# Connectors.net
KiCad netlist of a schematic drawn in Altium Designer
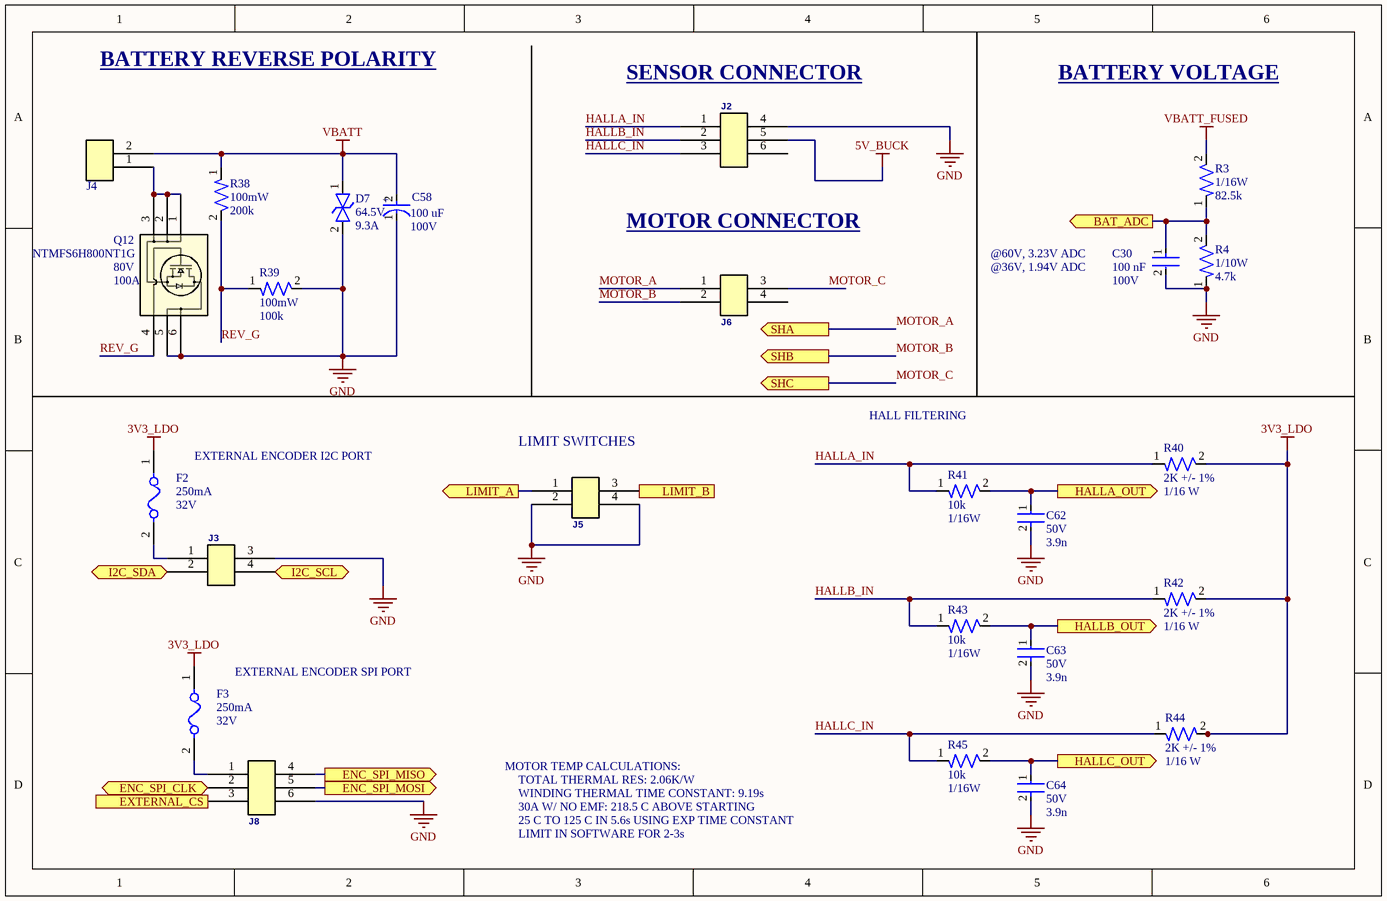
[diagram p0: Connectors.SchDoc]

(export (version "E")
  (design (tool "Eeschema 10.0.6"))
  (components
    (comp (ref "C30")
      (value "GRM188R72A104KA35D")
      (footprint "CAP-0603")
      (description "CAP CER 100NF 100V X7R 0603")
      (fields (field (name "CAPACITANCE") "100 nF") (field (name "VOLTAGE") "100V"))
      (libsource (lib "JLC_25") (part "CAP-1U-0002"))
    )
    (comp (ref "C58")
      (value "EEETK2A101AM")
      (footprint "CAP-100U-0001")
      (description "CAP ALUM 100UF 20% 100V SMD")
      (fields (field (name "VOLTAGE") "100V") (field (name "CAPACITANCE") "100 uF"))
      (libsource (lib "JLC_25") (part "CAP-100U-0001"))
    )
    (comp (ref "C62")
      (value "CC0402JRX7R9BB392")
      (footprint "CAP-0402")
      (description "3900 pF ±5% 50V Ceramic Capacitor X7R 0402 (1005 Metric)")
      (fields (field (name "VOLTAGE") "50V") (field (name "CAPACITANCE") "3.9n"))
      (libsource (lib "JLC_25") (part "CAP-3.9N-0001"))
    )
    (comp (ref "C63")
      (value "CC0402JRX7R9BB392")
      (footprint "CAP-0402")
      (description "3900 pF ±5% 50V Ceramic Capacitor X7R 0402 (1005 Metric)")
      (fields (field (name "VOLTAGE") "50V") (field (name "CAPACITANCE") "3.9n"))
      (libsource (lib "JLC_25") (part "CAP-3.9N-0001"))
    )
    (comp (ref "C64")
      (value "CC0402JRX7R9BB392")
      (footprint "CAP-0402")
      (description "3900 pF ±5% 50V Ceramic Capacitor X7R 0402 (1005 Metric)")
      (fields (field (name "VOLTAGE") "50V") (field (name "CAPACITANCE") "3.9n"))
      (libsource (lib "JLC_25") (part "CAP-3.9N-0001"))
    )
    (comp (ref "D7")
      (value "SMBJ40CA")
      (footprint "DO-214AA (SMBJ)")
      (description "TVS DIODE 40VWM 64.5VC DO214AA")
      (fields (field (name "VOLTAGE RATING") "64.5V") (field (name "CURRENT RATING") "9.3A"))
      (libsource (lib "JLC_25") (part "DIO-TVS-0001"))
    )
    (comp (ref "F2")
      (value "0467.250NRHF")
      (footprint "RES-0603")
      (description "FUSE BRD MT 250MA 32VAC 32VDC")
      (fields (field (name "FUSE CURRENT") "250mA") (field (name "VOLTAGE RATING") "32V"))
      (libsource (lib "JLC_25") (part "FUSE-0002"))
    )
    (comp (ref "F3")
      (value "0467.250NRHF")
      (footprint "RES-0603")
      (description "FUSE BRD MT 250MA 32VAC 32VDC")
      (fields (field (name "FUSE CURRENT") "250mA") (field (name "VOLTAGE RATING") "32V"))
      (libsource (lib "JLC_25") (part "FUSE-0002"))
    )
    (comp (ref "J2")
      (value "Molex 43045-0612")
      (footprint "CONN-6POS-0001")
      (description "CONN HEADER VERT 6POS 3MM")
      (libsource (lib "JLC_25") (part "CONN-6POS-0001"))
    )
    (comp (ref "J3")
      (value "Molex 43045-0412")
      (footprint "CONN-4POS-0002")
      (description "CONN HEADER VERT 4POS 3MM")
      (libsource (lib "JLC_25") (part "CONN-4POS-0002"))
    )
    (comp (ref "J4")
      (value "1546927-2")
      (footprint "CONN-1546927-2")
      (libsource (lib "JLC_25") (part "CONN-2POS-0003"))
    )
    (comp (ref "J5")
      (value "Molex 43045-0412")
      (footprint "CONN-4POS-0002")
      (description "CONN HEADER VERT 4POS 3MM")
      (libsource (lib "JLC_25") (part "CONN-4POS-0002"))
    )
    (comp (ref "J6")
      (value "Molex 43045-0412")
      (footprint "CONN-4POS-0002")
      (description "CONN HEADER VERT 4POS 3MM")
      (libsource (lib "JLC_25") (part "CONN-4POS-0002"))
    )
    (comp (ref "J8")
      (value "Molex 43045-0612")
      (footprint "CONN-6POS-0001")
      (description "CONN HEADER VERT 6POS 3MM")
      (libsource (lib "JLC_25") (part "CONN-6POS-0001"))
    )
    (comp (ref "Q12")
      (value "NTMFS6H800NT1G")
      (footprint "DFN6_5X6_SO8FL_488AA_ONS")
      (description "N-Channel 80 V 28A (Ta), 203A (Tc) 3.8W (Ta), 200W (Tc) Surface Mount 5-DFN (5x6) (8-SOFL)")
      (fields
        (field (name "MANUFACTURER_PART_NUMBER") "TPH2R506PL")
        (field (name "VDSS") "80V")
        (field (name "DRAIN CURRENT") "100A")
      )
      (libsource (lib "MasterLib") (part "NTMFS6H800NT1G"))
    )
    (comp (ref "R3")
      (value "RC0402FR-0782K5L")
      (footprint "RES-0402")
      (description "82.5 kOhms ±1% 0.063W, 1/16W Chip Resistor 0402 (1005 Metric) Moisture Resistant Thick Film")
      (fields
        (field (name "TOLERANCE") "1%")
        (field (name "POWER") "1/16W")
        (field (name "RESISTANCE") "82.5k")
      )
      (libsource (lib "JLC_25") (part "RES-82.5k-0001"))
    )
    (comp (ref "R4")
      (value "RC0603FR-074K7L")
      (footprint "RES-0603")
      (description "RES 4.7K OHM 1% 1/10W 0603")
      (fields
        (field (name "TOLERANCE") "1%")
        (field (name "POWER") "1/10W")
        (field (name "RESISTANCE") "4.7k")
      )
      (libsource (lib "JLC_25") (part "RES-4.7k-0001"))
    )
    (comp (ref "R38")
      (value "RC0603FR-07200KL")
      (footprint "RES-0603")
      (description "RES SMD 200K OHM 1% 1/10W 0603")
      (fields
        (field (name "TOLERANCE") "1%")
        (field (name "POWER") "100mW")
        (field (name "RESISTANCE") "200k")
      )
      (libsource (lib "JLC_25") (part "RES-200k-0001"))
    )
    (comp (ref "R39")
      (value "RC0603FR-07100KL")
      (footprint "RES-0603")
      (description "RES SMD 100K OHM 1% 1/10W 0603")
      (fields
        (field (name "TOLERANCE") "1%")
        (field (name "POWER") "100mW")
        (field (name "RESISTANCE") "100k")
      )
      (libsource (lib "JLC_25") (part "RES-100k-0001"))
    )
    (comp (ref "R40")
      (value "RC0402FR-072KP")
      (footprint "RES-0402")
      (description "2 kOhms ±1% 0.063W, 1/16W Chip Resistor 0402 (1005 Metric) Thick Film")
      (fields (field (name "RESISTANCE") "2K +/- 1%") (field (name "POWER") "1/16 W"))
      (libsource (lib "MasterLib") (part "RES-2K-0001"))
    )
    (comp (ref "R41")
      (value "RC0402FR-0710KL")
      (footprint "RES-0402")
      (description "RES 10K OHM 1% 1/16W 0402")
      (fields
        (field (name "TOLERANCE") "1%")
        (field (name "RESISTANCE") "10k")
        (field (name "POWER") "1/16W")
      )
      (libsource (lib "JLC_25") (part "RES-10k-0001"))
    )
    (comp (ref "R42")
      (value "RC0402FR-072KP")
      (footprint "RES-0402")
      (description "2 kOhms ±1% 0.063W, 1/16W Chip Resistor 0402 (1005 Metric) Thick Film")
      (fields (field (name "RESISTANCE") "2K +/- 1%") (field (name "POWER") "1/16 W"))
      (libsource (lib "MasterLib") (part "RES-2K-0001"))
    )
    (comp (ref "R43")
      (value "RC0402FR-0710KL")
      (footprint "RES-0402")
      (description "RES 10K OHM 1% 1/16W 0402")
      (fields
        (field (name "TOLERANCE") "1%")
        (field (name "RESISTANCE") "10k")
        (field (name "POWER") "1/16W")
      )
      (libsource (lib "JLC_25") (part "RES-10k-0001"))
    )
    (comp (ref "R44")
      (value "RC0402FR-072KP")
      (footprint "RES-0402")
      (description "2 kOhms ±1% 0.063W, 1/16W Chip Resistor 0402 (1005 Metric) Thick Film")
      (fields (field (name "RESISTANCE") "2K +/- 1%") (field (name "POWER") "1/16 W"))
      (libsource (lib "MasterLib") (part "RES-2K-0001"))
    )
    (comp (ref "R45")
      (value "RC0402FR-0710KL")
      (footprint "RES-0402")
      (description "RES 10K OHM 1% 1/16W 0402")
      (fields
        (field (name "TOLERANCE") "1%")
        (field (name "RESISTANCE") "10k")
        (field (name "POWER") "1/16W")
      )
      (libsource (lib "JLC_25") (part "RES-10k-0001"))
    )
  )
  (nets
    (net (code "1") (name "/BAT_ADC") (class "Default")
      (node (ref "C30") (pin "1") (pinfunction "1_1") (pintype "passive"))
      (node (ref "R3") (pin "1") (pinfunction "1_1") (pintype "passive"))
      (node (ref "R4") (pin "2") (pinfunction "2_2") (pintype "passive"))
    )
    (net (code "2") (name "/ENC_SPI_CLK") (class "Default")
      (node (ref "J8") (pin "2") (pinfunction "2_2") (pintype "passive"))
    )
    (net (code "3") (name "/ENC_SPI_MISO") (class "Default")
      (node (ref "J8") (pin "4") (pinfunction "4_4") (pintype "passive"))
    )
    (net (code "4") (name "/ENC_SPI_MOSI") (class "Default")
      (node (ref "J8") (pin "5") (pinfunction "5_5") (pintype "passive"))
    )
    (net (code "5") (name "/EXTERNAL_CS") (class "Default")
      (node (ref "J8") (pin "3") (pinfunction "3_3") (pintype "passive"))
    )
    (net (code "6") (name "/HALLA_IN") (class "Default")
      (node (ref "J2") (pin "1") (pinfunction "7_1") (pintype "passive"))
      (node (ref "R40") (pin "1") (pinfunction "1_1") (pintype "passive"))
      (node (ref "R41") (pin "1") (pinfunction "1_1") (pintype "passive"))
    )
    (net (code "7") (name "/HALLA_OUT") (class "Default")
      (node (ref "C62") (pin "1") (pinfunction "1_1") (pintype "passive"))
      (node (ref "R41") (pin "2") (pinfunction "2_2") (pintype "passive"))
    )
    (net (code "8") (name "/HALLB_IN") (class "Default")
      (node (ref "J2") (pin "2") (pinfunction "2_2") (pintype "passive"))
      (node (ref "R42") (pin "1") (pinfunction "1_1") (pintype "passive"))
      (node (ref "R43") (pin "1") (pinfunction "1_1") (pintype "passive"))
    )
    (net (code "9") (name "/HALLB_OUT") (class "Default")
      (node (ref "C63") (pin "1") (pinfunction "1_1") (pintype "passive"))
      (node (ref "R43") (pin "2") (pinfunction "2_2") (pintype "passive"))
    )
    (net (code "10") (name "/HALLC_IN") (class "Default")
      (node (ref "J2") (pin "3") (pinfunction "3_3") (pintype "passive"))
      (node (ref "R44") (pin "1") (pinfunction "1_1") (pintype "passive"))
      (node (ref "R45") (pin "1") (pinfunction "1_1") (pintype "passive"))
    )
    (net (code "11") (name "/HALLC_OUT") (class "Default")
      (node (ref "C64") (pin "1") (pinfunction "1_1") (pintype "passive"))
      (node (ref "R45") (pin "2") (pinfunction "2_2") (pintype "passive"))
    )
    (net (code "12") (name "/I2C_SCL") (class "Default")
      (node (ref "J3") (pin "4") (pinfunction "4_4") (pintype "passive"))
    )
    (net (code "13") (name "/I2C_SDA") (class "Default")
      (node (ref "J3") (pin "2") (pinfunction "2_2") (pintype "passive"))
    )
    (net (code "14") (name "/LIMIT_A") (class "Default")
      (node (ref "J5") (pin "1") (pinfunction "1_1") (pintype "passive"))
    )
    (net (code "15") (name "/LIMIT_B") (class "Default")
      (node (ref "J5") (pin "3") (pinfunction "3_3") (pintype "passive"))
    )
    (net (code "16") (name "/MOTOR_A") (class "Default")
      (node (ref "J6") (pin "1") (pinfunction "1_1") (pintype "passive"))
    )
    (net (code "17") (name "/MOTOR_B") (class "Default")
      (node (ref "J6") (pin "2") (pinfunction "2_2") (pintype "passive"))
    )
    (net (code "18") (name "/MOTOR_C") (class "Default")
      (node (ref "J6") (pin "3") (pinfunction "3_3") (pintype "passive"))
    )
    (net (code "19") (name "/REV_G") (class "Default")
      (node (ref "Q12") (pin "4") (pinfunction "4_4") (pintype "passive"))
      (node (ref "R38") (pin "2") (pinfunction "2_2") (pintype "passive"))
      (node (ref "R39") (pin "1") (pinfunction "1_1") (pintype "passive"))
    )
    (net (code "20") (name "3V3_LDO") (class "Default")
      (node (ref "F2") (pin "1") (pinfunction "1_1") (pintype "passive"))
      (node (ref "F3") (pin "1") (pinfunction "1_1") (pintype "passive"))
      (node (ref "R40") (pin "2") (pinfunction "2_2") (pintype "passive"))
      (node (ref "R42") (pin "2") (pinfunction "2_2") (pintype "passive"))
      (node (ref "R44") (pin "2") (pinfunction "2_2") (pintype "passive"))
    )
    (net (code "21") (name "5V_BUCK") (class "Default")
      (node (ref "J2") (pin "5") (pinfunction "5_5") (pintype "passive"))
    )
    (net (code "22") (name "GND") (class "Default")
      (node (ref "C30") (pin "2") (pinfunction "2_2") (pintype "passive"))
      (node (ref "C58") (pin "1") (pinfunction "2_1") (pintype "passive"))
      (node (ref "C62") (pin "2") (pinfunction "2_2") (pintype "passive"))
      (node (ref "C63") (pin "2") (pinfunction "2_2") (pintype "passive"))
      (node (ref "C64") (pin "2") (pinfunction "2_2") (pintype "passive"))
      (node (ref "D7") (pin "2") (pintype "passive"))
      (node (ref "J2") (pin "4") (pinfunction "4_4") (pintype "passive"))
      (node (ref "J3") (pin "3") (pinfunction "3_3") (pintype "passive"))
      (node (ref "J5") (pin "2") (pinfunction "2_2") (pintype "passive"))
      (node (ref "J5") (pin "4") (pinfunction "4_4") (pintype "passive"))
      (node (ref "J8") (pin "6") (pinfunction "6_6") (pintype "passive"))
      (node (ref "Q12") (pin "5") (pinfunction "5_5") (pintype "passive"))
      (node (ref "Q12") (pin "6") (pinfunction "6_6") (pintype "passive"))
      (node (ref "R39") (pin "2") (pinfunction "2_2") (pintype "passive"))
      (node (ref "R4") (pin "1") (pinfunction "1_1") (pintype "passive"))
    )
    (net (code "23") (name "Net-(F2-Pad2)") (class "Default")
      (node (ref "F2") (pin "2") (pinfunction "2_2") (pintype "passive"))
      (node (ref "J3") (pin "1") (pinfunction "1_1") (pintype "passive"))
    )
    (net (code "24") (name "Net-(J4-7)") (class "Default")
      (node (ref "J4") (pin "1") (pinfunction "7_1") (pintype "passive"))
      (node (ref "Q12") (pin "1") (pinfunction "1_1") (pintype "passive"))
      (node (ref "Q12") (pin "2") (pinfunction "2_2") (pintype "passive"))
      (node (ref "Q12") (pin "3") (pinfunction "3_3") (pintype "passive"))
    )
    (net (code "25") (name "Net-(J8-7)") (class "Default")
      (node (ref "F3") (pin "2") (pinfunction "2_2") (pintype "passive"))
      (node (ref "J8") (pin "1") (pinfunction "7_1") (pintype "passive"))
    )
    (net (code "26") (name "VBATT") (class "Default")
      (node (ref "C58") (pin "2") (pinfunction "1_2") (pintype "passive"))
      (node (ref "D7") (pin "1") (pintype "passive"))
      (node (ref "J4") (pin "2") (pinfunction "8_2") (pintype "passive"))
      (node (ref "R38") (pin "1") (pinfunction "1_1") (pintype "passive"))
    )
    (net (code "27") (name "VBATT_FUSED") (class "Default")
      (node (ref "R3") (pin "2") (pinfunction "2_2") (pintype "passive"))
    )
    (net (code "28") (name "unconnected-(J2-Pad6)") (class "Default")
      (node (ref "J2") (pin "6") (pinfunction "6_6") (pintype "passive"))
    )
    (net (code "29") (name "unconnected-(J6-Pad4)") (class "Default")
      (node (ref "J6") (pin "4") (pinfunction "4_4") (pintype "passive"))
    )
  )
)
